# Gas_Sampler-Top.net
KiCad netlist of a schematic drawn in Altium Designer
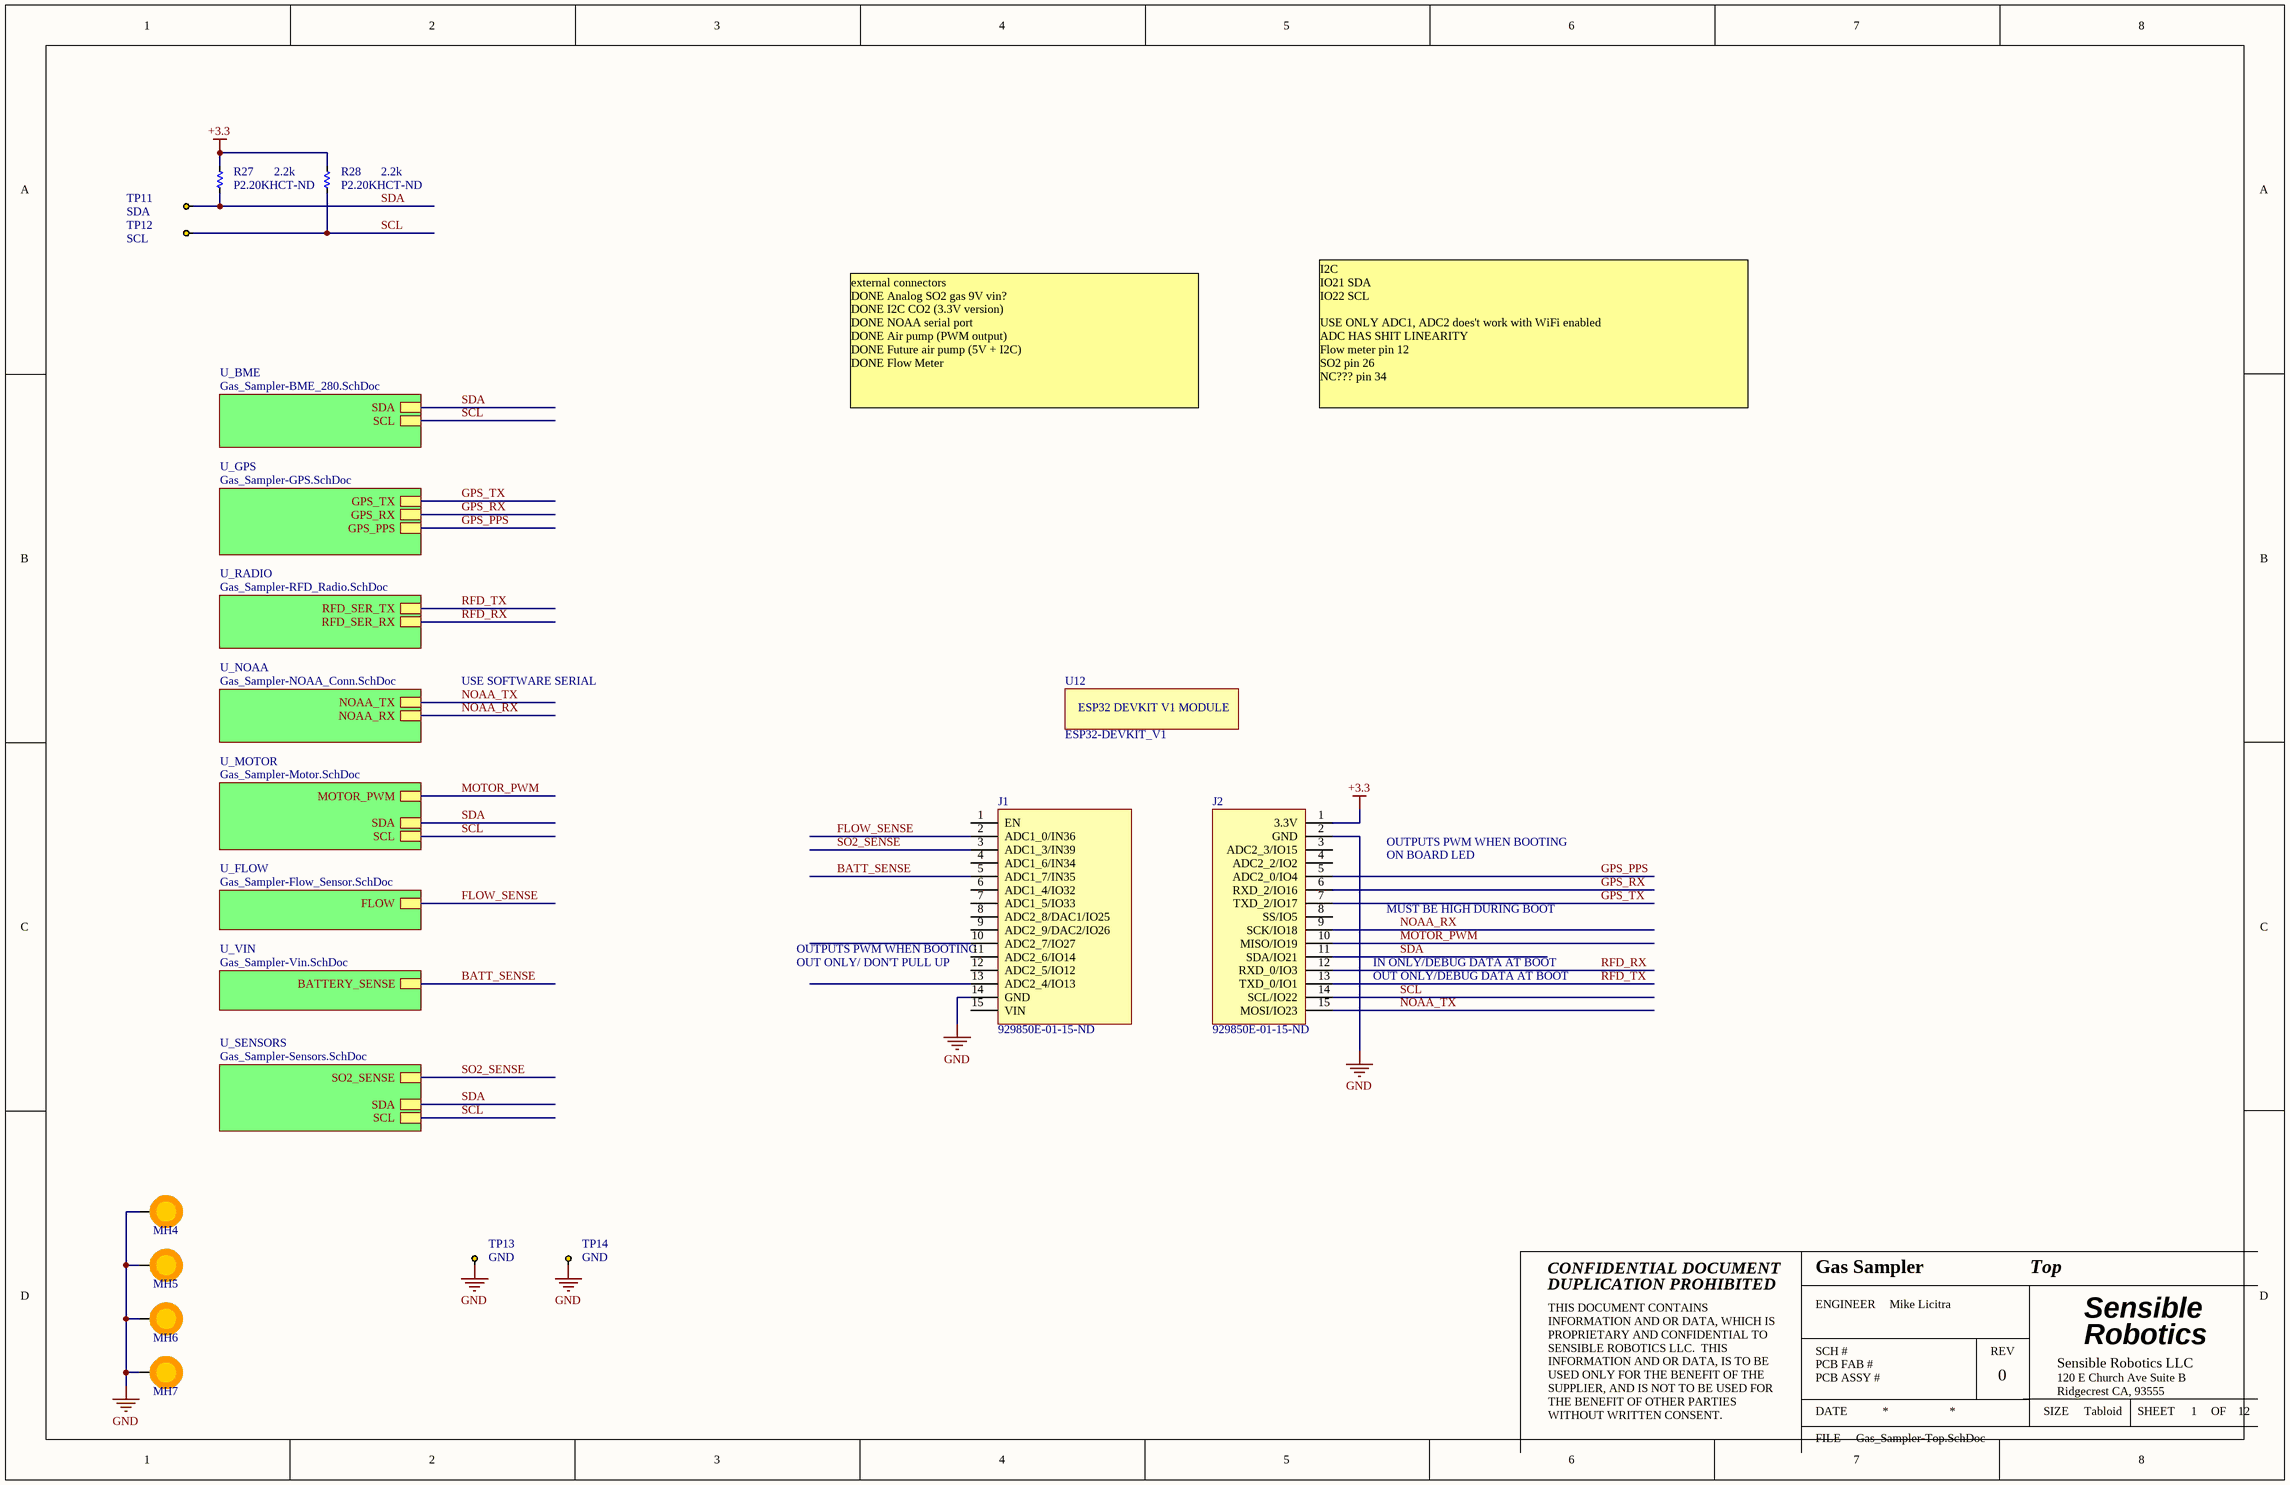
[diagram p0: Gas_Sampler-Top.SchDoc]

(export (version "E")
  (design (tool "Eeschema 10.0.6"))
  (components
    (comp (ref "J1")
      (value "ESP32-DEVKIT_V1-30PIN_MODULE_J2")
      (footprint "SOCKET_1X15_POS_0.1_INCH")
      (description "CONN_SOCKETS_1X15_POS_0.1_INCH")
      (fields
        (field (name "MANUFACTURER") "3M")
        (field (name "MANUFACTURER PART NUMBER") "929850-01-15-RA")
        (field (name "SUPPLIER PART NUMBER 1") "929850E-01-15-ND")
      )
      (libsource (lib "modules") (part "ESP32-DEVKIT_V1-30PIN_MODULE_J2"))
    )
    (comp (ref "J2")
      (value "ESP32-DEVKIT_V1-30PIN_MODULE_J3")
      (footprint "SOCKET_1X15_POS_0.1_INCH")
      (description "CONN_SOCKETS_1X15_POS_0.1_INCH")
      (fields
        (field (name "MANUFACTURER") "3M")
        (field (name "MANUFACTURER PART NUMBER") "929850-01-15-RA")
        (field (name "SUPPLIER PART NUMBER 1") "929850E-01-15-ND")
      )
      (libsource (lib "modules") (part "ESP32-DEVKIT_V1-30PIN_MODULE_J3"))
    )
    (comp (ref "MH4") (value "SCREW") (footprint "SCREW_M3") (libsource (lib "mechanical") (part "SCREW")))
    (comp (ref "MH5") (value "SCREW") (footprint "SCREW_M3") (libsource (lib "mechanical") (part "SCREW")))
    (comp (ref "MH6") (value "SCREW") (footprint "SCREW_M3") (libsource (lib "mechanical") (part "SCREW")))
    (comp (ref "MH7") (value "SCREW") (footprint "SCREW_M3") (libsource (lib "mechanical") (part "SCREW")))
    (comp (ref "R27")
      (value "2.2k")
      (footprint "R0603")
      (description "RES 2.2K OHM 1/10W 1% 0603 SMD")
      (fields
        (field (name "MANUFACTURER") "Panasonic Electronic Components")
        (field (name "MANUFACTURER PART NUMBER") "ERJ-3EKF2201V")
        (field (name "SUPPLIER PART NUMBER 1") "P2.20KHCT-ND")
      )
      (libsource (lib "resistor") (part "RES_0603_2.2K_OHM_1/10W_1%"))
    )
    (comp (ref "R28")
      (value "2.2k")
      (footprint "R0603")
      (description "RES 2.2K OHM 1/10W 1% 0603 SMD")
      (fields
        (field (name "MANUFACTURER") "Panasonic Electronic Components")
        (field (name "MANUFACTURER PART NUMBER") "ERJ-3EKF2201V")
        (field (name "SUPPLIER PART NUMBER 1") "P2.20KHCT-ND")
      )
      (libsource (lib "resistor") (part "RES_0603_2.2K_OHM_1/10W_1%"))
    )
    (comp (ref "TP11")
      (value "SDA")
      (footprint "TP_KEYSTONE_5001")
      (description "PC TEST POINT TH RING")
      (fields
        (field (name "MANUFACTURER") "Keystone Electronics")
        (field (name "MANUFACTURER PART NUMBER") "5001")
      )
      (libsource (lib "miscellaneous") (part "TEST_KEYSTONE5001"))
    )
    (comp (ref "TP12")
      (value "SCL")
      (footprint "TP_KEYSTONE_5001")
      (description "PC TEST POINT TH RING")
      (fields
        (field (name "MANUFACTURER") "Keystone Electronics")
        (field (name "MANUFACTURER PART NUMBER") "5001")
      )
      (libsource (lib "miscellaneous") (part "TEST_KEYSTONE5001"))
    )
    (comp (ref "TP13")
      (value "GND")
      (footprint "TP_KEYSTONE_5001")
      (description "PC TEST POINT TH RING")
      (fields
        (field (name "MANUFACTURER") "Keystone Electronics")
        (field (name "MANUFACTURER PART NUMBER") "5001")
      )
      (libsource (lib "miscellaneous") (part "TEST_KEYSTONE5001"))
    )
    (comp (ref "TP14")
      (value "GND")
      (footprint "TP_KEYSTONE_5001")
      (description "PC TEST POINT TH RING")
      (fields
        (field (name "MANUFACTURER") "Keystone Electronics")
        (field (name "MANUFACTURER PART NUMBER") "5001")
      )
      (libsource (lib "miscellaneous") (part "TEST_KEYSTONE5001"))
    )
    (comp (ref "U12")
      (value "ESP32-DEVKIT_V1")
      (footprint "ESP32_DEVKITV1_MODULE")
      (description "ESP32-DEVKIT V1 MODULE")
      (libsource (lib "modules") (part "ESP32-DEVKIT_V1"))
    )
  )
  (nets
    (net (code "1") (name "+3.3") (class "Default")
      (node (ref "J2") (pin "1") (pinfunction "3.3V_1") (pintype "passive"))
      (node (ref "R27") (pin "2") (pintype "passive"))
      (node (ref "R28") (pin "2") (pintype "passive"))
    )
    (net (code "2") (name "/BATT_SENSE") (class "Default")
      (node (ref "J1") (pin "5") (pinfunction "ADC1_7/IN35_5") (pintype "passive"))
    )
    (net (code "3") (name "/FLOW_SENSE") (class "Default")
      (node (ref "J1") (pin "2") (pinfunction "ADC1_0/IN36_2") (pintype "passive"))
    )
    (net (code "4") (name "/GPS_PPS") (class "Default")
      (node (ref "J2") (pin "5") (pinfunction "ADC2_0/IO4_5") (pintype "passive"))
    )
    (net (code "5") (name "/GPS_RX") (class "Default")
      (node (ref "J2") (pin "6") (pinfunction "RXD_2/IO16_6") (pintype "passive"))
    )
    (net (code "6") (name "/GPS_TX") (class "Default")
      (node (ref "J2") (pin "7") (pinfunction "TXD_2/IO17_7") (pintype "passive"))
    )
    (net (code "7") (name "/MOTOR_PWM") (class "Default")
      (node (ref "J2") (pin "10") (pinfunction "MISO/IO19_10") (pintype "passive"))
    )
    (net (code "8") (name "/NOAA_RX") (class "Default")
      (node (ref "J2") (pin "9") (pinfunction "SCK/IO18_9") (pintype "passive"))
    )
    (net (code "9") (name "/NOAA_TX") (class "Default")
      (node (ref "J2") (pin "15") (pinfunction "MOSI/IO23_15") (pintype "passive"))
    )
    (net (code "10") (name "/RFD_RX") (class "Default")
      (node (ref "J2") (pin "12") (pinfunction "RXD_0/IO3_12") (pintype "passive"))
    )
    (net (code "11") (name "/RFD_TX") (class "Default")
      (node (ref "J2") (pin "13") (pinfunction "TXD_0/IO1_13") (pintype "passive"))
    )
    (net (code "12") (name "/SCL") (class "Default")
      (node (ref "J2") (pin "14") (pinfunction "SCL/IO22_14") (pintype "passive"))
      (node (ref "R28") (pin "1") (pintype "passive"))
      (node (ref "TP12") (pin "1") (pintype "passive"))
    )
    (net (code "13") (name "/SDA") (class "Default")
      (node (ref "J2") (pin "11") (pinfunction "SDA/IO21_11") (pintype "passive"))
      (node (ref "R27") (pin "1") (pintype "passive"))
      (node (ref "TP11") (pin "1") (pintype "passive"))
    )
    (net (code "14") (name "/SO2_SENSE") (class "Default")
      (node (ref "J1") (pin "3") (pinfunction "ADC1_3/IN39_3") (pintype "passive"))
    )
    (net (code "15") (name "GND") (class "Default")
      (node (ref "J1") (pin "14") (pinfunction "GND_14") (pintype "passive"))
      (node (ref "J2") (pin "2") (pinfunction "GND_2") (pintype "passive"))
      (node (ref "MH4") (pin "1") (pintype "passive"))
      (node (ref "MH5") (pin "1") (pintype "passive"))
      (node (ref "MH6") (pin "1") (pintype "passive"))
      (node (ref "MH7") (pin "1") (pintype "passive"))
      (node (ref "TP13") (pin "1") (pintype "passive"))
      (node (ref "TP14") (pin "1") (pintype "passive"))
    )
    (net (code "16") (name "unconnected-(J1-ADC1_4{slash}IO32-Pad6)") (class "Default")
      (node (ref "J1") (pin "6") (pinfunction "ADC1_4/IO32_6") (pintype "passive"))
    )
    (net (code "17") (name "unconnected-(J1-ADC1_5{slash}IO33-Pad7)") (class "Default")
      (node (ref "J1") (pin "7") (pinfunction "ADC1_5/IO33_7") (pintype "passive"))
    )
    (net (code "18") (name "unconnected-(J1-ADC1_6{slash}IN34-Pad4)") (class "Default")
      (node (ref "J1") (pin "4") (pinfunction "ADC1_6/IN34_4") (pintype "passive"))
    )
    (net (code "19") (name "unconnected-(J1-ADC2_4{slash}IO13-Pad13)") (class "Default")
      (node (ref "J1") (pin "13") (pinfunction "ADC2_4/IO13_13") (pintype "passive"))
    )
    (net (code "20") (name "unconnected-(J1-ADC2_5{slash}IO12-Pad12)") (class "Default")
      (node (ref "J1") (pin "12") (pinfunction "ADC2_5/IO12_12") (pintype "passive"))
    )
    (net (code "21") (name "unconnected-(J1-ADC2_6{slash}IO14-Pad11)") (class "Default")
      (node (ref "J1") (pin "11") (pinfunction "ADC2_6/IO14_11") (pintype "passive"))
    )
    (net (code "22") (name "unconnected-(J1-ADC2_7{slash}IO27-Pad10)") (class "Default")
      (node (ref "J1") (pin "10") (pinfunction "ADC2_7/IO27_10") (pintype "passive"))
    )
    (net (code "23") (name "unconnected-(J1-ADC2_8{slash}DAC1{slash}IO25-Pad8)") (class "Default")
      (node (ref "J1") (pin "8") (pinfunction "ADC2_8/DAC1/IO25_8") (pintype "passive"))
    )
    (net (code "24") (name "unconnected-(J1-ADC2_9{slash}DAC2{slash}IO26-Pad9)") (class "Default")
      (node (ref "J1") (pin "9") (pinfunction "ADC2_9/DAC2/IO26_9") (pintype "passive"))
    )
    (net (code "25") (name "unconnected-(J1-EN-Pad1)") (class "Default")
      (node (ref "J1") (pin "1") (pinfunction "EN_1") (pintype "passive"))
    )
    (net (code "26") (name "unconnected-(J1-VIN-Pad15)") (class "Default")
      (node (ref "J1") (pin "15") (pinfunction "VIN_15") (pintype "passive"))
    )
    (net (code "27") (name "unconnected-(J2-ADC2_2{slash}IO2-Pad4)") (class "Default")
      (node (ref "J2") (pin "4") (pinfunction "ADC2_2/IO2_4") (pintype "passive"))
    )
    (net (code "28") (name "unconnected-(J2-ADC2_3{slash}IO15-Pad3)") (class "Default")
      (node (ref "J2") (pin "3") (pinfunction "ADC2_3/IO15_3") (pintype "passive"))
    )
    (net (code "29") (name "unconnected-(J2-SS{slash}IO5-Pad8)") (class "Default")
      (node (ref "J2") (pin "8") (pinfunction "SS/IO5_8") (pintype "passive"))
    )
  )
)
